# power_converter.net
KiCad netlist of a schematic drawn in EAGLE
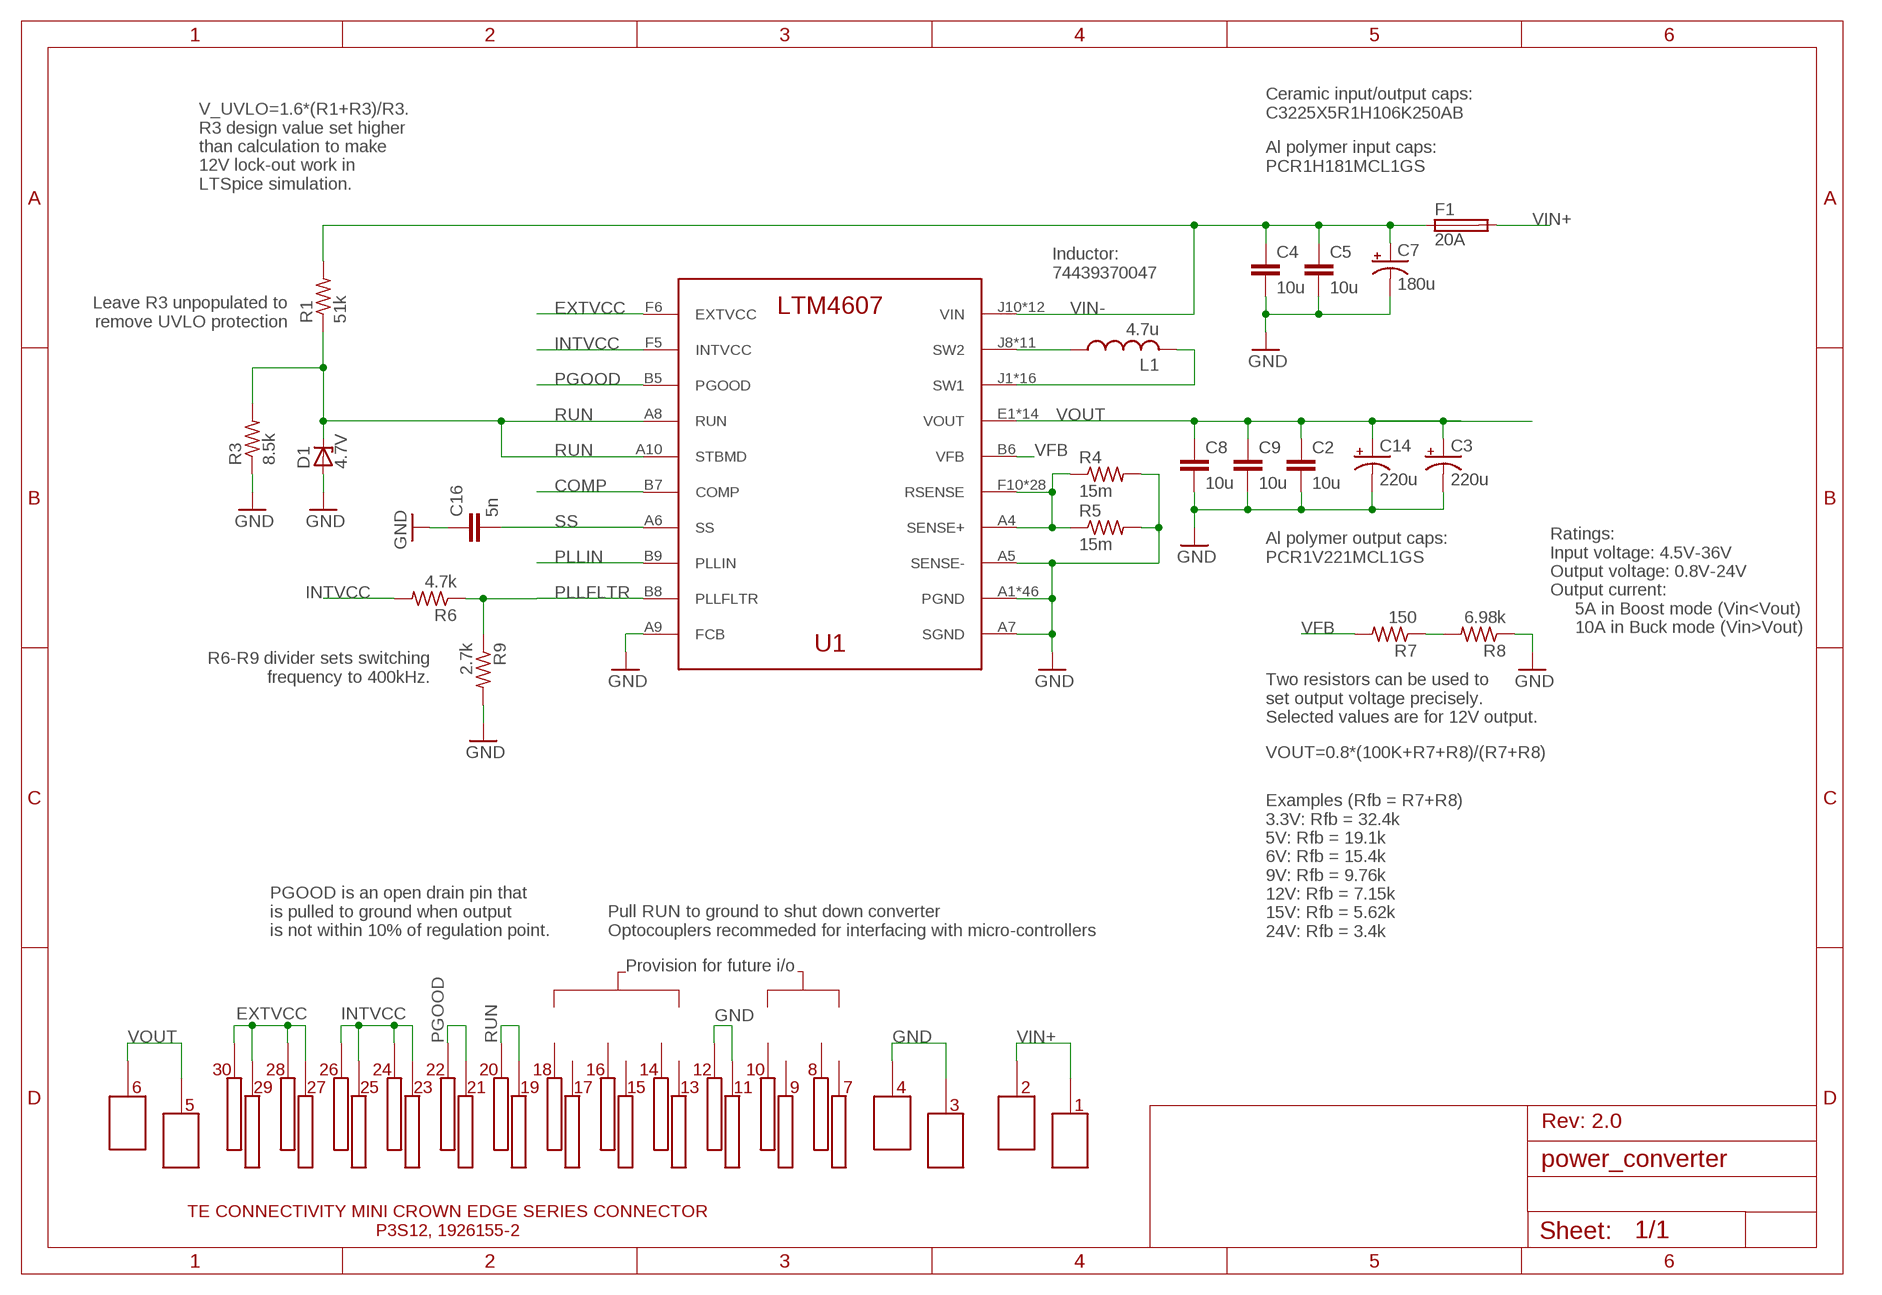
[diagram p0: schematic, sheet 1]

(export (version "E")
  (design (tool "Eeschema 10.0.6"))
  (components
    (comp (ref "C2")
      (value "10u")
      (footprint "eagle-import:C1210")
      (libsource (lib "eagle-import") (part "C-EUC1210"))
    )
    (comp (ref "C3")
      (value "220u")
      (footprint "eagle-import:PCR1V221MCL1GS")
      (libsource (lib "eagle-import") (part "PCR1V221MCL1GS"))
    )
    (comp (ref "C4")
      (value "10u")
      (footprint "eagle-import:C1210")
      (libsource (lib "eagle-import") (part "C-EUC1210"))
    )
    (comp (ref "C5")
      (value "10u")
      (footprint "eagle-import:C1210")
      (libsource (lib "eagle-import") (part "C-EUC1210"))
    )
    (comp (ref "C7")
      (value "180u")
      (footprint "eagle-import:PCR1H181MCL1GS")
      (libsource (lib "eagle-import") (part "PCR1H181MCL1GS"))
    )
    (comp (ref "C8")
      (value "10u")
      (footprint "eagle-import:C1210")
      (libsource (lib "eagle-import") (part "C-EUC1210"))
    )
    (comp (ref "C9")
      (value "10u")
      (footprint "eagle-import:C1210")
      (libsource (lib "eagle-import") (part "C-EUC1210"))
    )
    (comp (ref "C14")
      (value "220u")
      (footprint "eagle-import:PCR1V221MCL1GS")
      (libsource (lib "eagle-import") (part "PCR1V221MCL1GS"))
    )
    (comp (ref "C16")
      (value "5n")
      (footprint "eagle-import:C0603")
      (libsource (lib "eagle-import") (part "C-EUC0603"))
    )
    (comp (ref "D1")
      (value "4.7V")
      (footprint "eagle-import:SOD80C")
      (libsource (lib "eagle-import") (part "ZENER-DIODESOD80C"))
    )
    (comp (ref "F1")
      (value "20A")
      (footprint "eagle-import:R1206")
      (libsource (lib "eagle-import") (part "501_FUSE"))
    )
    (comp (ref "L1")
      (value "4.7u")
      (footprint "eagle-import:PA4343.472ANLT")
      (libsource (lib "eagle-import") (part "PA4343.472ANLT"))
    )
    (comp (ref "R1")
      (value "51k")
      (footprint "eagle-import:R0603")
      (libsource (lib "eagle-import") (part "R-US_R0603"))
    )
    (comp (ref "R3")
      (value "8.5k")
      (footprint "eagle-import:R0603")
      (libsource (lib "eagle-import") (part "R-US_R0603"))
    )
    (comp (ref "R4")
      (value "15m")
      (footprint "eagle-import:R1206")
      (libsource (lib "eagle-import") (part "R-US_R1206"))
    )
    (comp (ref "R5")
      (value "15m")
      (footprint "eagle-import:R1206")
      (libsource (lib "eagle-import") (part "R-US_R1206"))
    )
    (comp (ref "R6")
      (value "4.7k")
      (footprint "eagle-import:R0603")
      (libsource (lib "eagle-import") (part "R-US_R0603"))
    )
    (comp (ref "R7")
      (value "150")
      (footprint "eagle-import:R0603")
      (libsource (lib "eagle-import") (part "R-US_R0603"))
    )
    (comp (ref "R8")
      (value "6.98k")
      (footprint "eagle-import:R0603")
      (libsource (lib "eagle-import") (part "R-US_R0603"))
    )
    (comp (ref "R9")
      (value "2.7k")
      (footprint "eagle-import:R0603")
      (libsource (lib "eagle-import") (part "R-US_R0603"))
    )
    (comp (ref "U$1")
      (value "1926155-2_CARD")
      (footprint "eagle-import:1926155-2_CARD")
      (libsource (lib "eagle-import") (part "1926155-2_CARD"))
    )
    (comp (ref "U1")
      (value "LTM4607EVPBF")
      (footprint "eagle-import:LGA-141")
      (fields (field (name "MANUFACTURER_PART_NUMBER") "LTM4607EV#PBF"))
      (libsource (lib "eagle-import") (part "LTM4607EVPBF"))
    )
  )
  (nets
    (net (code "1") (name "/COMP") (class "Default")
      (node (ref "U1") (pin "B7") (pinfunction "COMP_B7") (pintype "power_in"))
    )
    (net (code "2") (name "/EXTVCC") (class "Default")
      (node (ref "U$1") (pin "P$27") (pinfunction "P$27_P$27") (pintype "bidirectional"))
      (node (ref "U$1") (pin "P$28") (pinfunction "P$28_P$28") (pintype "bidirectional"))
      (node (ref "U$1") (pin "P$29") (pinfunction "P$29_P$29") (pintype "bidirectional"))
      (node (ref "U$1") (pin "P$30") (pinfunction "P$30_P$30") (pintype "bidirectional"))
      (node (ref "U1") (pin "F6") (pinfunction "EXTVCC_F6") (pintype "power_in"))
    )
    (net (code "3") (name "/INTVCC") (class "Default")
      (node (ref "R6") (pin "2") (pinfunction "2_2") (pintype "passive"))
      (node (ref "U$1") (pin "P$23") (pinfunction "P$23_P$23") (pintype "bidirectional"))
      (node (ref "U$1") (pin "P$24") (pinfunction "P$24_P$24") (pintype "bidirectional"))
      (node (ref "U$1") (pin "P$25") (pinfunction "P$25_P$25") (pintype "bidirectional"))
      (node (ref "U$1") (pin "P$26") (pinfunction "P$26_P$26") (pintype "bidirectional"))
      (node (ref "U1") (pin "F5") (pinfunction "INTVCC_F5") (pintype "power_in"))
    )
    (net (code "4") (name "/PGOOD") (class "Default")
      (node (ref "U$1") (pin "P$21") (pinfunction "P$21_P$21") (pintype "bidirectional"))
      (node (ref "U$1") (pin "P$22") (pinfunction "P$22_P$22") (pintype "bidirectional"))
      (node (ref "U1") (pin "B5") (pinfunction "PGOOD_B5") (pintype "power_in"))
    )
    (net (code "5") (name "/PLLFLTR") (class "Default")
      (node (ref "R6") (pin "1") (pinfunction "1_1") (pintype "passive"))
      (node (ref "R9") (pin "1") (pinfunction "1_1") (pintype "passive"))
      (node (ref "U1") (pin "B8") (pinfunction "PLLFLTR_B8") (pintype "power_in"))
    )
    (net (code "6") (name "/PLLIN") (class "Default")
      (node (ref "U1") (pin "B9") (pinfunction "PLLIN_B9") (pintype "power_in"))
    )
    (net (code "7") (name "/RUN") (class "Default")
      (node (ref "D1") (pin "C") (pinfunction "C_C") (pintype "passive"))
      (node (ref "R1") (pin "1") (pinfunction "1_1") (pintype "passive"))
      (node (ref "R3") (pin "2") (pinfunction "2_2") (pintype "passive"))
      (node (ref "U$1") (pin "P$19") (pinfunction "P$19_P$19") (pintype "bidirectional"))
      (node (ref "U$1") (pin "P$20") (pinfunction "P$20_P$20") (pintype "bidirectional"))
      (node (ref "U1") (pin "A10") (pinfunction "STBMD_A10") (pintype "power_in"))
      (node (ref "U1") (pin "A8") (pinfunction "RUN_A8") (pintype "power_in"))
    )
    (net (code "8") (name "/SS") (class "Default")
      (node (ref "C16") (pin "2") (pinfunction "2_2") (pintype "passive"))
      (node (ref "U1") (pin "A6") (pinfunction "SS_A6") (pintype "power_in"))
    )
    (net (code "9") (name "/VFB") (class "Default")
      (node (ref "R7") (pin "2") (pinfunction "2_2") (pintype "passive"))
      (node (ref "U1") (pin "B6") (pinfunction "VFB_B6") (pintype "power_in"))
    )
    (net (code "10") (name "/VIN+") (class "Default")
      (node (ref "F1") (pin "2") (pinfunction "2_2") (pintype "passive"))
      (node (ref "U$1") (pin "P$1") (pinfunction "P$1_P$1") (pintype "bidirectional"))
      (node (ref "U$1") (pin "P$2") (pinfunction "P$2_P$2") (pintype "bidirectional"))
    )
    (net (code "11") (name "/VIN-") (class "Default")
      (node (ref "C4") (pin "1") (pinfunction "1_1") (pintype "passive"))
      (node (ref "C5") (pin "1") (pinfunction "1_1") (pintype "passive"))
      (node (ref "C7") (pin "POS") (pinfunction "+_POS") (pintype "passive"))
      (node (ref "F1") (pin "1") (pinfunction "1_1") (pintype "passive"))
      (node (ref "R1") (pin "2") (pinfunction "2_2") (pintype "passive"))
      (node (ref "U1") (pin "J10") (pinfunction "VIN_J10") (pintype "power_in"))
      (node (ref "U1") (pin "J11") (pinfunction "VIN_J11") (pintype "power_in"))
      (node (ref "U1") (pin "J12") (pinfunction "VIN_J12") (pintype "power_in"))
      (node (ref "U1") (pin "K10") (pinfunction "VIN_K10") (pintype "power_in"))
      (node (ref "U1") (pin "K11") (pinfunction "VIN_K11") (pintype "power_in"))
      (node (ref "U1") (pin "K12") (pinfunction "VIN_K12") (pintype "power_in"))
      (node (ref "U1") (pin "L10") (pinfunction "VIN_L10") (pintype "power_in"))
      (node (ref "U1") (pin "L11") (pinfunction "VIN_L11") (pintype "power_in"))
      (node (ref "U1") (pin "L12") (pinfunction "VIN_L12") (pintype "power_in"))
      (node (ref "U1") (pin "M10") (pinfunction "VIN_M10") (pintype "power_in"))
      (node (ref "U1") (pin "M11") (pinfunction "VIN_M11") (pintype "power_in"))
      (node (ref "U1") (pin "M12") (pinfunction "VIN_M12") (pintype "power_in"))
    )
    (net (code "12") (name "/VOUT") (class "Default")
      (node (ref "C14") (pin "POS") (pinfunction "+_POS") (pintype "passive"))
      (node (ref "C2") (pin "1") (pinfunction "1_1") (pintype "passive"))
      (node (ref "C3") (pin "POS") (pinfunction "+_POS") (pintype "passive"))
      (node (ref "C8") (pin "1") (pinfunction "1_1") (pintype "passive"))
      (node (ref "C9") (pin "1") (pinfunction "1_1") (pintype "passive"))
      (node (ref "U$1") (pin "P$5") (pinfunction "P$5_P$5") (pintype "bidirectional"))
      (node (ref "U$1") (pin "P$6") (pinfunction "P$6_P$6") (pintype "bidirectional"))
      (node (ref "U1") (pin "E1") (pinfunction "VOUT_E1") (pintype "power_in"))
      (node (ref "U1") (pin "E2") (pinfunction "VOUT_E2") (pintype "power_in"))
      (node (ref "U1") (pin "F1") (pinfunction "VOUT_F1") (pintype "power_in"))
      (node (ref "U1") (pin "F2") (pinfunction "VOUT_F2") (pintype "power_in"))
      (node (ref "U1") (pin "F3") (pinfunction "VOUT_F3") (pintype "power_in"))
      (node (ref "U1") (pin "F4") (pinfunction "VOUT_F4") (pintype "power_in"))
      (node (ref "U1") (pin "G1") (pinfunction "VOUT_G1") (pintype "power_in"))
      (node (ref "U1") (pin "G2") (pinfunction "VOUT_G2") (pintype "power_in"))
      (node (ref "U1") (pin "G3") (pinfunction "VOUT_G3") (pintype "power_in"))
      (node (ref "U1") (pin "G4") (pinfunction "VOUT_G4") (pintype "power_in"))
      (node (ref "U1") (pin "H1") (pinfunction "VOUT_H1") (pintype "power_in"))
      (node (ref "U1") (pin "H2") (pinfunction "VOUT_H2") (pintype "power_in"))
      (node (ref "U1") (pin "H3") (pinfunction "VOUT_H3") (pintype "power_in"))
      (node (ref "U1") (pin "H4") (pinfunction "VOUT_H4") (pintype "power_in"))
    )
    (net (code "13") (name "GND") (class "Default")
      (node (ref "C14") (pin "NEG") (pinfunction "-_NEG") (pintype "passive"))
      (node (ref "C16") (pin "1") (pinfunction "1_1") (pintype "passive"))
      (node (ref "C2") (pin "2") (pinfunction "2_2") (pintype "passive"))
      (node (ref "C3") (pin "NEG") (pinfunction "-_NEG") (pintype "passive"))
      (node (ref "C4") (pin "2") (pinfunction "2_2") (pintype "passive"))
      (node (ref "C5") (pin "2") (pinfunction "2_2") (pintype "passive"))
      (node (ref "C7") (pin "NEG") (pinfunction "-_NEG") (pintype "passive"))
      (node (ref "C8") (pin "2") (pinfunction "2_2") (pintype "passive"))
      (node (ref "C9") (pin "2") (pinfunction "2_2") (pintype "passive"))
      (node (ref "D1") (pin "A") (pinfunction "A_A") (pintype "passive"))
      (node (ref "R3") (pin "1") (pinfunction "1_1") (pintype "passive"))
      (node (ref "R4") (pin "2") (pinfunction "2_2") (pintype "passive"))
      (node (ref "R5") (pin "2") (pinfunction "2_2") (pintype "passive"))
      (node (ref "R8") (pin "1") (pinfunction "1_1") (pintype "passive"))
      (node (ref "R9") (pin "2") (pinfunction "2_2") (pintype "passive"))
      (node (ref "U$1") (pin "P$11") (pinfunction "P$11_P$11") (pintype "bidirectional"))
      (node (ref "U$1") (pin "P$12") (pinfunction "P$12_P$12") (pintype "bidirectional"))
      (node (ref "U$1") (pin "P$3") (pinfunction "P$3_P$3") (pintype "bidirectional"))
      (node (ref "U$1") (pin "P$4") (pinfunction "P$4_P$4") (pintype "bidirectional"))
      (node (ref "U1") (pin "A1") (pinfunction "PGND_A1") (pintype "power_in"))
      (node (ref "U1") (pin "A11") (pinfunction "PGND_A11") (pintype "power_in"))
      (node (ref "U1") (pin "A12") (pinfunction "PGND_A12") (pintype "power_in"))
      (node (ref "U1") (pin "A2") (pinfunction "PGND_A2") (pintype "power_in"))
      (node (ref "U1") (pin "A3") (pinfunction "PGND_A3") (pintype "power_in"))
      (node (ref "U1") (pin "A5") (pinfunction "SENSE-_A5") (pintype "power_in"))
      (node (ref "U1") (pin "A7") (pinfunction "SGND_A7") (pintype "power_in"))
      (node (ref "U1") (pin "A9") (pinfunction "FCB_A9") (pintype "power_in"))
      (node (ref "U1") (pin "B1") (pinfunction "PGND_B1") (pintype "power_in"))
      (node (ref "U1") (pin "B10") (pinfunction "PGND_B10") (pintype "power_in"))
      (node (ref "U1") (pin "B11") (pinfunction "PGND_B11") (pintype "power_in"))
      (node (ref "U1") (pin "B12") (pinfunction "PGND_B12") (pintype "power_in"))
      (node (ref "U1") (pin "B2") (pinfunction "PGND_B2") (pintype "power_in"))
      (node (ref "U1") (pin "B3") (pinfunction "PGND_B3") (pintype "power_in"))
      (node (ref "U1") (pin "B4") (pinfunction "PGND_B4") (pintype "power_in"))
      (node (ref "U1") (pin "C1") (pinfunction "PGND_C1") (pintype "power_in"))
      (node (ref "U1") (pin "C10") (pinfunction "PGND_C10") (pintype "power_in"))
      (node (ref "U1") (pin "C11") (pinfunction "PGND_C11") (pintype "power_in"))
      (node (ref "U1") (pin "C12") (pinfunction "PGND_C12") (pintype "power_in"))
      (node (ref "U1") (pin "C2") (pinfunction "PGND_C2") (pintype "power_in"))
      (node (ref "U1") (pin "C3") (pinfunction "PGND_C3") (pintype "power_in"))
      (node (ref "U1") (pin "C4") (pinfunction "PGND_C4") (pintype "power_in"))
      (node (ref "U1") (pin "C5") (pinfunction "PGND_C5") (pintype "power_in"))
      (node (ref "U1") (pin "C6") (pinfunction "PGND_C6") (pintype "power_in"))
      (node (ref "U1") (pin "C7") (pinfunction "PGND_C7") (pintype "power_in"))
      (node (ref "U1") (pin "C8") (pinfunction "PGND_C8") (pintype "power_in"))
      (node (ref "U1") (pin "C9") (pinfunction "PGND_C9") (pintype "power_in"))
      (node (ref "U1") (pin "D1") (pinfunction "PGND_D1") (pintype "power_in"))
      (node (ref "U1") (pin "D10") (pinfunction "PGND_D10") (pintype "power_in"))
      (node (ref "U1") (pin "D11") (pinfunction "PGND_D11") (pintype "power_in"))
      (node (ref "U1") (pin "D12") (pinfunction "PGND_D12") (pintype "power_in"))
      (node (ref "U1") (pin "D2") (pinfunction "PGND_D2") (pintype "power_in"))
      (node (ref "U1") (pin "D3") (pinfunction "PGND_D3") (pintype "power_in"))
      (node (ref "U1") (pin "D4") (pinfunction "PGND_D4") (pintype "power_in"))
      (node (ref "U1") (pin "D5") (pinfunction "PGND_D5") (pintype "power_in"))
      (node (ref "U1") (pin "D6") (pinfunction "PGND_D6") (pintype "power_in"))
      (node (ref "U1") (pin "D7") (pinfunction "PGND_D7") (pintype "power_in"))
      (node (ref "U1") (pin "D8") (pinfunction "PGND_D8") (pintype "power_in"))
      (node (ref "U1") (pin "D9") (pinfunction "PGND_D9") (pintype "power_in"))
      (node (ref "U1") (pin "E10") (pinfunction "PGND_E10") (pintype "power_in"))
      (node (ref "U1") (pin "E11") (pinfunction "PGND_E11") (pintype "power_in"))
      (node (ref "U1") (pin "E12") (pinfunction "PGND_E12") (pintype "power_in"))
      (node (ref "U1") (pin "E3") (pinfunction "PGND_E3") (pintype "power_in"))
      (node (ref "U1") (pin "E4") (pinfunction "PGND_E4") (pintype "power_in"))
      (node (ref "U1") (pin "E5") (pinfunction "PGND_E5") (pintype "power_in"))
      (node (ref "U1") (pin "E6") (pinfunction "PGND_E6") (pintype "power_in"))
      (node (ref "U1") (pin "E7") (pinfunction "PGND_E7") (pintype "power_in"))
      (node (ref "U1") (pin "E8") (pinfunction "PGND_E8") (pintype "power_in"))
      (node (ref "U1") (pin "E9") (pinfunction "PGND_E9") (pintype "power_in"))
    )
    (net (code "14") (name "Net-(L1-1)") (class "Default")
      (node (ref "L1") (pin "P$1") (pinfunction "1_P$1") (pintype "passive"))
      (node (ref "U1") (pin "J8") (pinfunction "SW2_J8") (pintype "power_in"))
      (node (ref "U1") (pin "J9") (pinfunction "SW2_J9") (pintype "power_in"))
      (node (ref "U1") (pin "K7") (pinfunction "SW2_K7") (pintype "power_in"))
      (node (ref "U1") (pin "K8") (pinfunction "SW2_K8") (pintype "power_in"))
      (node (ref "U1") (pin "K9") (pinfunction "SW2_K9") (pintype "power_in"))
      (node (ref "U1") (pin "L7") (pinfunction "SW2_L7") (pintype "power_in"))
      (node (ref "U1") (pin "L8") (pinfunction "SW2_L8") (pintype "power_in"))
      (node (ref "U1") (pin "L9") (pinfunction "SW2_L9") (pintype "power_in"))
      (node (ref "U1") (pin "M7") (pinfunction "SW2_M7") (pintype "power_in"))
      (node (ref "U1") (pin "M8") (pinfunction "SW2_M8") (pintype "power_in"))
      (node (ref "U1") (pin "M9") (pinfunction "SW2_M9") (pintype "power_in"))
    )
    (net (code "15") (name "Net-(L1-2)") (class "Default")
      (node (ref "L1") (pin "P$2") (pinfunction "2_P$2") (pintype "passive"))
      (node (ref "U1") (pin "J1") (pinfunction "SW1_J1") (pintype "power_in"))
      (node (ref "U1") (pin "J2") (pinfunction "SW1_J2") (pintype "power_in"))
      (node (ref "U1") (pin "J3") (pinfunction "SW1_J3") (pintype "power_in"))
      (node (ref "U1") (pin "J4") (pinfunction "SW1_J4") (pintype "power_in"))
      (node (ref "U1") (pin "K1") (pinfunction "SW1_K1") (pintype "power_in"))
      (node (ref "U1") (pin "K2") (pinfunction "SW1_K2") (pintype "power_in"))
      (node (ref "U1") (pin "K3") (pinfunction "SW1_K3") (pintype "power_in"))
      (node (ref "U1") (pin "K4") (pinfunction "SW1_K4") (pintype "power_in"))
      (node (ref "U1") (pin "L1") (pinfunction "SW1_L1") (pintype "power_in"))
      (node (ref "U1") (pin "L2") (pinfunction "SW1_L2") (pintype "power_in"))
      (node (ref "U1") (pin "L3") (pinfunction "SW1_L3") (pintype "power_in"))
      (node (ref "U1") (pin "L4") (pinfunction "SW1_L4") (pintype "power_in"))
      (node (ref "U1") (pin "M1") (pinfunction "SW1_M1") (pintype "power_in"))
      (node (ref "U1") (pin "M2") (pinfunction "SW1_M2") (pintype "power_in"))
      (node (ref "U1") (pin "M3") (pinfunction "SW1_M3") (pintype "power_in"))
      (node (ref "U1") (pin "M4") (pinfunction "SW1_M4") (pintype "power_in"))
    )
    (net (code "16") (name "Net-(R7-Pad1)") (class "Default")
      (node (ref "R7") (pin "1") (pinfunction "1_1") (pintype "passive"))
      (node (ref "R8") (pin "2") (pinfunction "2_2") (pintype "passive"))
    )
    (net (code "17") (name "Net-(U1-SENSE+)") (class "Default")
      (node (ref "R4") (pin "1") (pinfunction "1_1") (pintype "passive"))
      (node (ref "R5") (pin "1") (pinfunction "1_1") (pintype "passive"))
      (node (ref "U1") (pin "A4") (pinfunction "SENSE+_A4") (pintype "power_in"))
      (node (ref "U1") (pin "F10") (pinfunction "RSENSE_F10") (pintype "power_in"))
      (node (ref "U1") (pin "F11") (pinfunction "RSENSE_F11") (pintype "power_in"))
      (node (ref "U1") (pin "F12") (pinfunction "RSENSE_F12") (pintype "power_in"))
      (node (ref "U1") (pin "G10") (pinfunction "RSENSE_G10") (pintype "power_in"))
      (node (ref "U1") (pin "G11") (pinfunction "RSENSE_G11") (pintype "power_in"))
      (node (ref "U1") (pin "G12") (pinfunction "RSENSE_G12") (pintype "power_in"))
      (node (ref "U1") (pin "G5") (pinfunction "RSENSE_G5") (pintype "power_in"))
      (node (ref "U1") (pin "G6") (pinfunction "RSENSE_G6") (pintype "power_in"))
      (node (ref "U1") (pin "G7") (pinfunction "RSENSE_G7") (pintype "power_in"))
      (node (ref "U1") (pin "G8") (pinfunction "RSENSE_G8") (pintype "power_in"))
      (node (ref "U1") (pin "G9") (pinfunction "RSENSE_G9") (pintype "power_in"))
      (node (ref "U1") (pin "H10") (pinfunction "RSENSE_H10") (pintype "power_in"))
      (node (ref "U1") (pin "H11") (pinfunction "RSENSE_H11") (pintype "power_in"))
      (node (ref "U1") (pin "H12") (pinfunction "RSENSE_H12") (pintype "power_in"))
      (node (ref "U1") (pin "H5") (pinfunction "RSENSE_H5") (pintype "power_in"))
      (node (ref "U1") (pin "H6") (pinfunction "RSENSE_H6") (pintype "power_in"))
      (node (ref "U1") (pin "H7") (pinfunction "RSENSE_H7") (pintype "power_in"))
      (node (ref "U1") (pin "H8") (pinfunction "RSENSE_H8") (pintype "power_in"))
      (node (ref "U1") (pin "H9") (pinfunction "RSENSE_H9") (pintype "power_in"))
      (node (ref "U1") (pin "J5") (pinfunction "RSENSE_J5") (pintype "power_in"))
      (node (ref "U1") (pin "J6") (pinfunction "RSENSE_J6") (pintype "power_in"))
      (node (ref "U1") (pin "J7") (pinfunction "RSENSE_J7") (pintype "power_in"))
      (node (ref "U1") (pin "K5") (pinfunction "RSENSE_K5") (pintype "power_in"))
      (node (ref "U1") (pin "K6") (pinfunction "RSENSE_K6") (pintype "power_in"))
      (node (ref "U1") (pin "L5") (pinfunction "RSENSE_L5") (pintype "power_in"))
      (node (ref "U1") (pin "L6") (pinfunction "RSENSE_L6") (pintype "power_in"))
      (node (ref "U1") (pin "M5") (pinfunction "RSENSE_M5") (pintype "power_in"))
      (node (ref "U1") (pin "M6") (pinfunction "RSENSE_M6") (pintype "power_in"))
    )
    (net (code "18") (name "unconnected-(U$1-PadP$7)") (class "Default")
      (node (ref "U$1") (pin "P$7") (pinfunction "P$7_P$7") (pintype "bidirectional"))
    )
    (net (code "19") (name "unconnected-(U$1-PadP$8)") (class "Default")
      (node (ref "U$1") (pin "P$8") (pinfunction "P$8_P$8") (pintype "bidirectional"))
    )
    (net (code "20") (name "unconnected-(U$1-PadP$9)") (class "Default")
      (node (ref "U$1") (pin "P$9") (pinfunction "P$9_P$9") (pintype "bidirectional"))
    )
    (net (code "21") (name "unconnected-(U$1-PadP$10)") (class "Default")
      (node (ref "U$1") (pin "P$10") (pinfunction "P$10_P$10") (pintype "bidirectional"))
    )
    (net (code "22") (name "unconnected-(U$1-PadP$13)") (class "Default")
      (node (ref "U$1") (pin "P$13") (pinfunction "P$13_P$13") (pintype "bidirectional"))
    )
    (net (code "23") (name "unconnected-(U$1-PadP$14)") (class "Default")
      (node (ref "U$1") (pin "P$14") (pinfunction "P$14_P$14") (pintype "bidirectional"))
    )
    (net (code "24") (name "unconnected-(U$1-PadP$15)") (class "Default")
      (node (ref "U$1") (pin "P$15") (pinfunction "P$15_P$15") (pintype "bidirectional"))
    )
    (net (code "25") (name "unconnected-(U$1-PadP$16)") (class "Default")
      (node (ref "U$1") (pin "P$16") (pinfunction "P$16_P$16") (pintype "bidirectional"))
    )
    (net (code "26") (name "unconnected-(U$1-PadP$17)") (class "Default")
      (node (ref "U$1") (pin "P$17") (pinfunction "P$17_P$17") (pintype "bidirectional"))
    )
    (net (code "27") (name "unconnected-(U$1-PadP$18)") (class "Default")
      (node (ref "U$1") (pin "P$18") (pinfunction "P$18_P$18") (pintype "bidirectional"))
    )
  )
)
